# har_DAA_PMIC_Programming.net
KiCad netlist of a schematic drawn in EAGLE
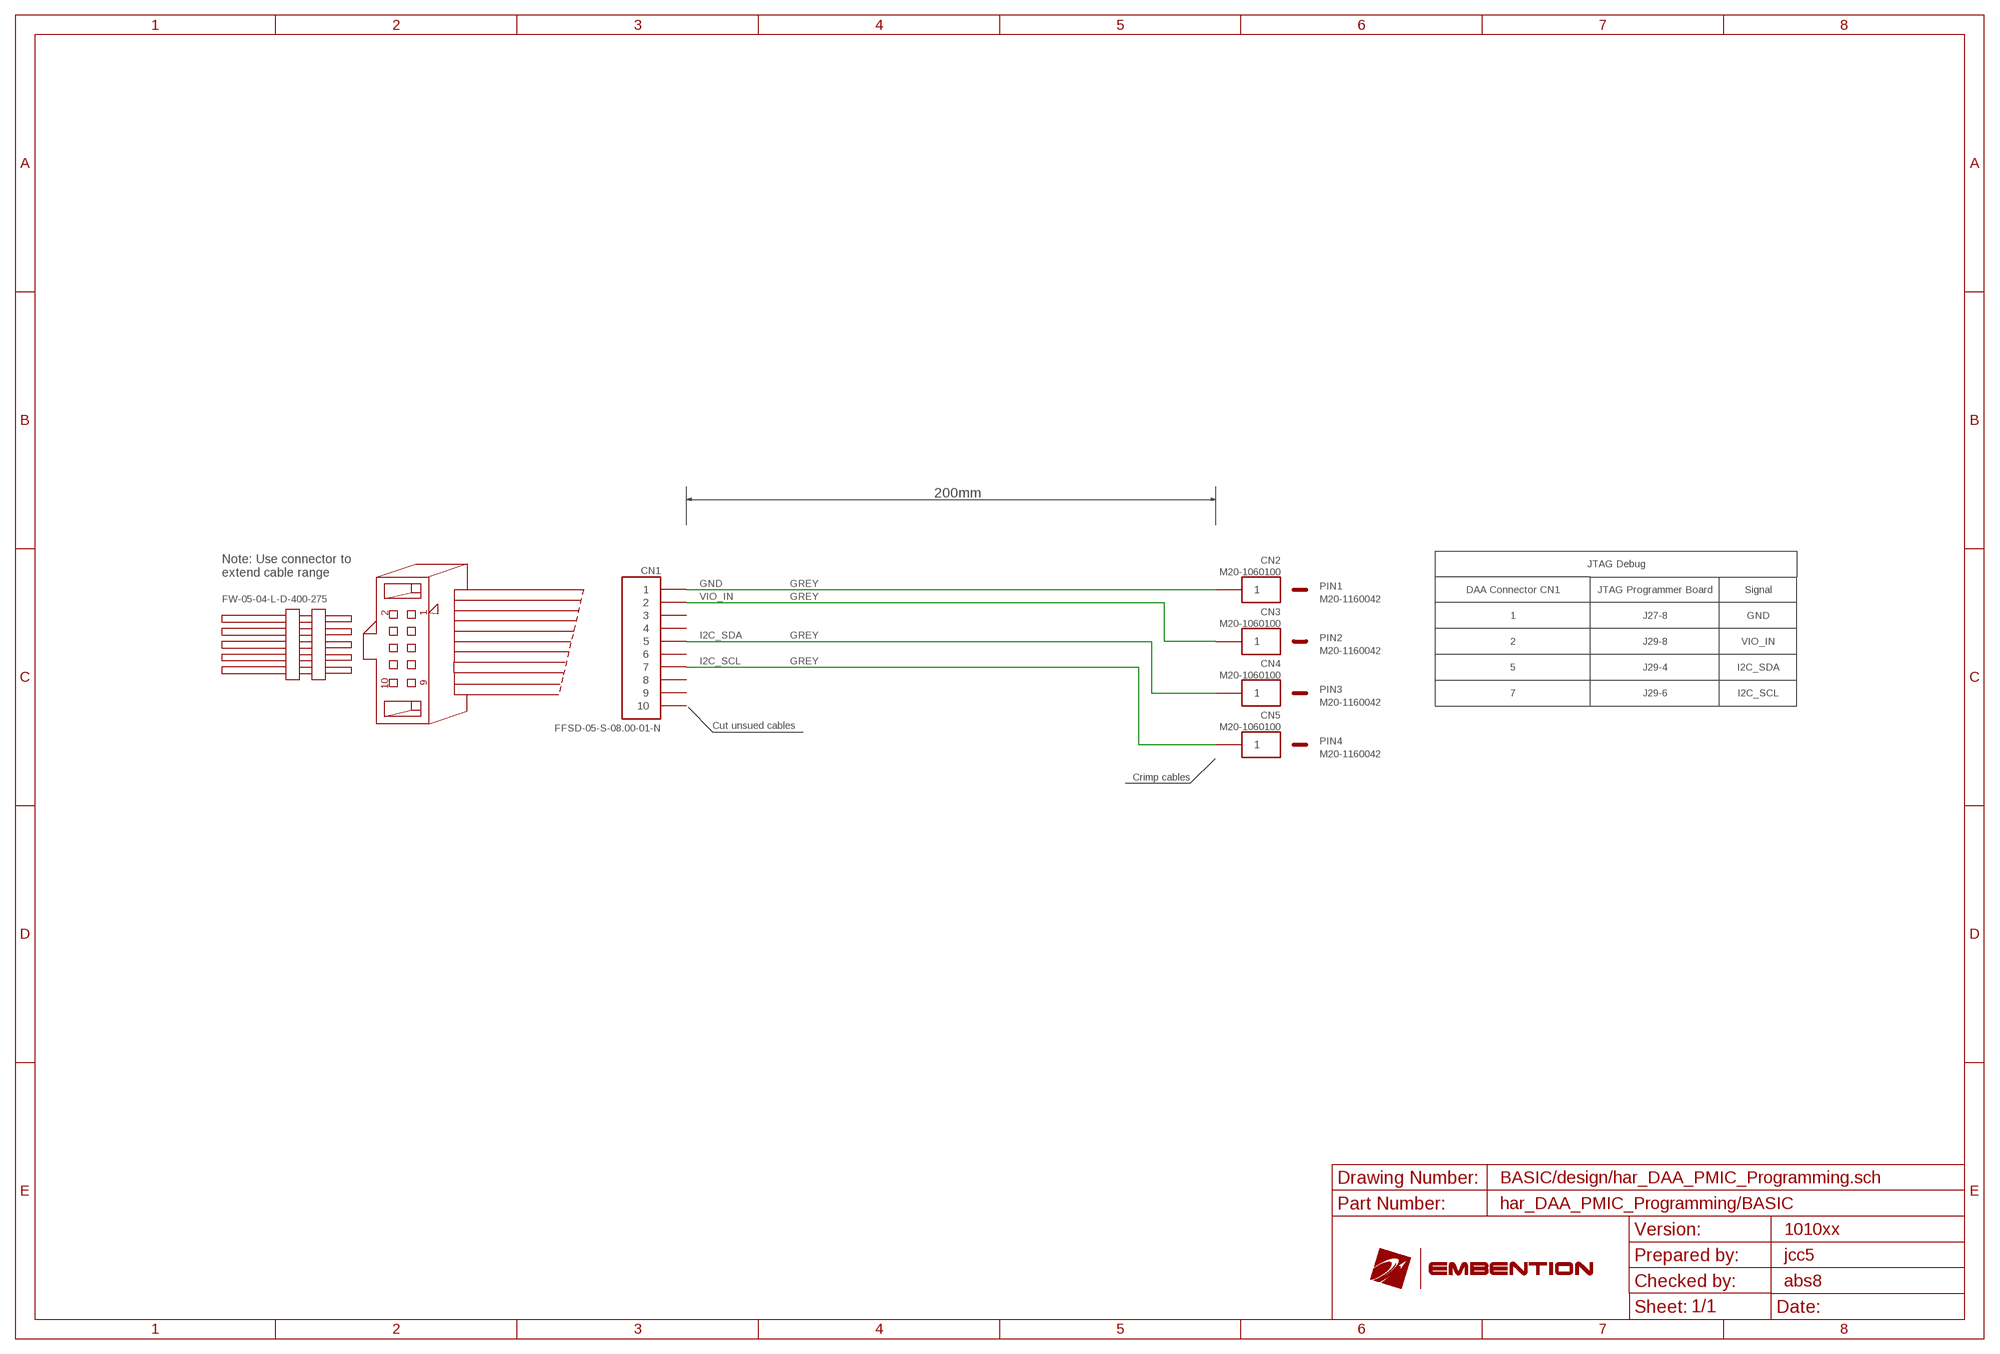
[diagram p0: schematic, sheet 1]

(export (version "E")
  (design (tool "Eeschema 10.0.6"))
  (components
    (comp (ref "CN1")
      (value "FFSD-05-S-08.00-01-N")
      (footprint "eagle-import:25-PIN")
      (libsource (lib "eagle-import") (part "10-PIN-NUM"))
    )
    (comp (ref "CN2")
      (value "M20-1060100")
      (footprint "eagle-import:2-PIN")
      (libsource (lib "eagle-import") (part "1-PIN-NUM"))
    )
    (comp (ref "CN3")
      (value "M20-1060100")
      (footprint "eagle-import:2-PIN")
      (libsource (lib "eagle-import") (part "1-PIN-NUM"))
    )
    (comp (ref "CN4")
      (value "M20-1060100")
      (footprint "eagle-import:2-PIN")
      (libsource (lib "eagle-import") (part "1-PIN-NUM"))
    )
    (comp (ref "CN5")
      (value "M20-1060100")
      (footprint "eagle-import:2-PIN")
      (libsource (lib "eagle-import") (part "1-PIN-NUM"))
    )
    (comp (ref "CN6")
      (value "FW-05-04-L-D-400-275")
      (footprint "eagle-import:CLAMP")
      (libsource (lib "eagle-import") (part "0-PIN"))
    )
    (comp (ref "PIN1")
      (value "M20-1160042")
      (footprint "eagle-import:1-PIN")
      (libsource (lib "eagle-import") (part "CONN-PIN"))
    )
    (comp (ref "PIN2")
      (value "M20-1160042")
      (footprint "eagle-import:1-PIN")
      (libsource (lib "eagle-import") (part "CONN-PIN"))
    )
    (comp (ref "PIN3")
      (value "M20-1160042")
      (footprint "eagle-import:1-PIN")
      (libsource (lib "eagle-import") (part "CONN-PIN"))
    )
    (comp (ref "PIN4")
      (value "M20-1160042")
      (footprint "eagle-import:1-PIN")
      (libsource (lib "eagle-import") (part "CONN-PIN"))
    )
  )
  (nets
    (net (code "1") (name "/GND") (class "Default")
      (node (ref "CN1") (pin "P$1") (pinfunction "1_P$1") (pintype "bidirectional"))
      (node (ref "CN2") (pin "P$1") (pinfunction "1_P$1") (pintype "bidirectional"))
    )
    (net (code "2") (name "/I2C_SCL") (class "Default")
      (node (ref "CN1") (pin "P$7") (pinfunction "7_P$7") (pintype "bidirectional"))
      (node (ref "CN5") (pin "P$1") (pinfunction "1_P$1") (pintype "bidirectional"))
    )
    (net (code "3") (name "/I2C_SDA") (class "Default")
      (node (ref "CN1") (pin "P$5") (pinfunction "5_P$5") (pintype "bidirectional"))
      (node (ref "CN4") (pin "P$1") (pinfunction "1_P$1") (pintype "bidirectional"))
    )
    (net (code "4") (name "/VIO_IN") (class "Default")
      (node (ref "CN1") (pin "P$2") (pinfunction "2_P$2") (pintype "bidirectional"))
      (node (ref "CN3") (pin "P$1") (pinfunction "1_P$1") (pintype "bidirectional"))
    )
    (net (code "5") (name "unconnected-(CN1-3-PadP$3)") (class "Default")
      (node (ref "CN1") (pin "P$3") (pinfunction "3_P$3") (pintype "bidirectional"))
    )
    (net (code "6") (name "unconnected-(CN1-4-PadP$4)") (class "Default")
      (node (ref "CN1") (pin "P$4") (pinfunction "4_P$4") (pintype "bidirectional"))
    )
    (net (code "7") (name "unconnected-(CN1-6-PadP$6)") (class "Default")
      (node (ref "CN1") (pin "P$6") (pinfunction "6_P$6") (pintype "bidirectional"))
    )
    (net (code "8") (name "unconnected-(CN1-8-PadP$8)") (class "Default")
      (node (ref "CN1") (pin "P$8") (pinfunction "8_P$8") (pintype "bidirectional"))
    )
    (net (code "9") (name "unconnected-(CN1-9-PadP$9)") (class "Default")
      (node (ref "CN1") (pin "P$9") (pinfunction "9_P$9") (pintype "bidirectional"))
    )
    (net (code "10") (name "unconnected-(CN1-10-PadP$10)") (class "Default")
      (node (ref "CN1") (pin "P$10") (pinfunction "10_P$10") (pintype "bidirectional"))
    )
    (net (code "11") (name "unconnected-(PIN1-PadP$1)") (class "Default")
      (node (ref "PIN1") (pin "P$1") (pinfunction "P$1_P$1") (pintype "bidirectional"))
    )
    (net (code "12") (name "unconnected-(PIN2-PadP$1)") (class "Default")
      (node (ref "PIN2") (pin "P$1") (pinfunction "P$1_P$1") (pintype "bidirectional"))
    )
    (net (code "13") (name "unconnected-(PIN3-PadP$1)") (class "Default")
      (node (ref "PIN3") (pin "P$1") (pinfunction "P$1_P$1") (pintype "bidirectional"))
    )
    (net (code "14") (name "unconnected-(PIN4-PadP$1)") (class "Default")
      (node (ref "PIN4") (pin "P$1") (pinfunction "P$1_P$1") (pintype "bidirectional"))
    )
  )
)
